# UC_Interface.net
KiCad netlist of a schematic drawn in Altium Designer
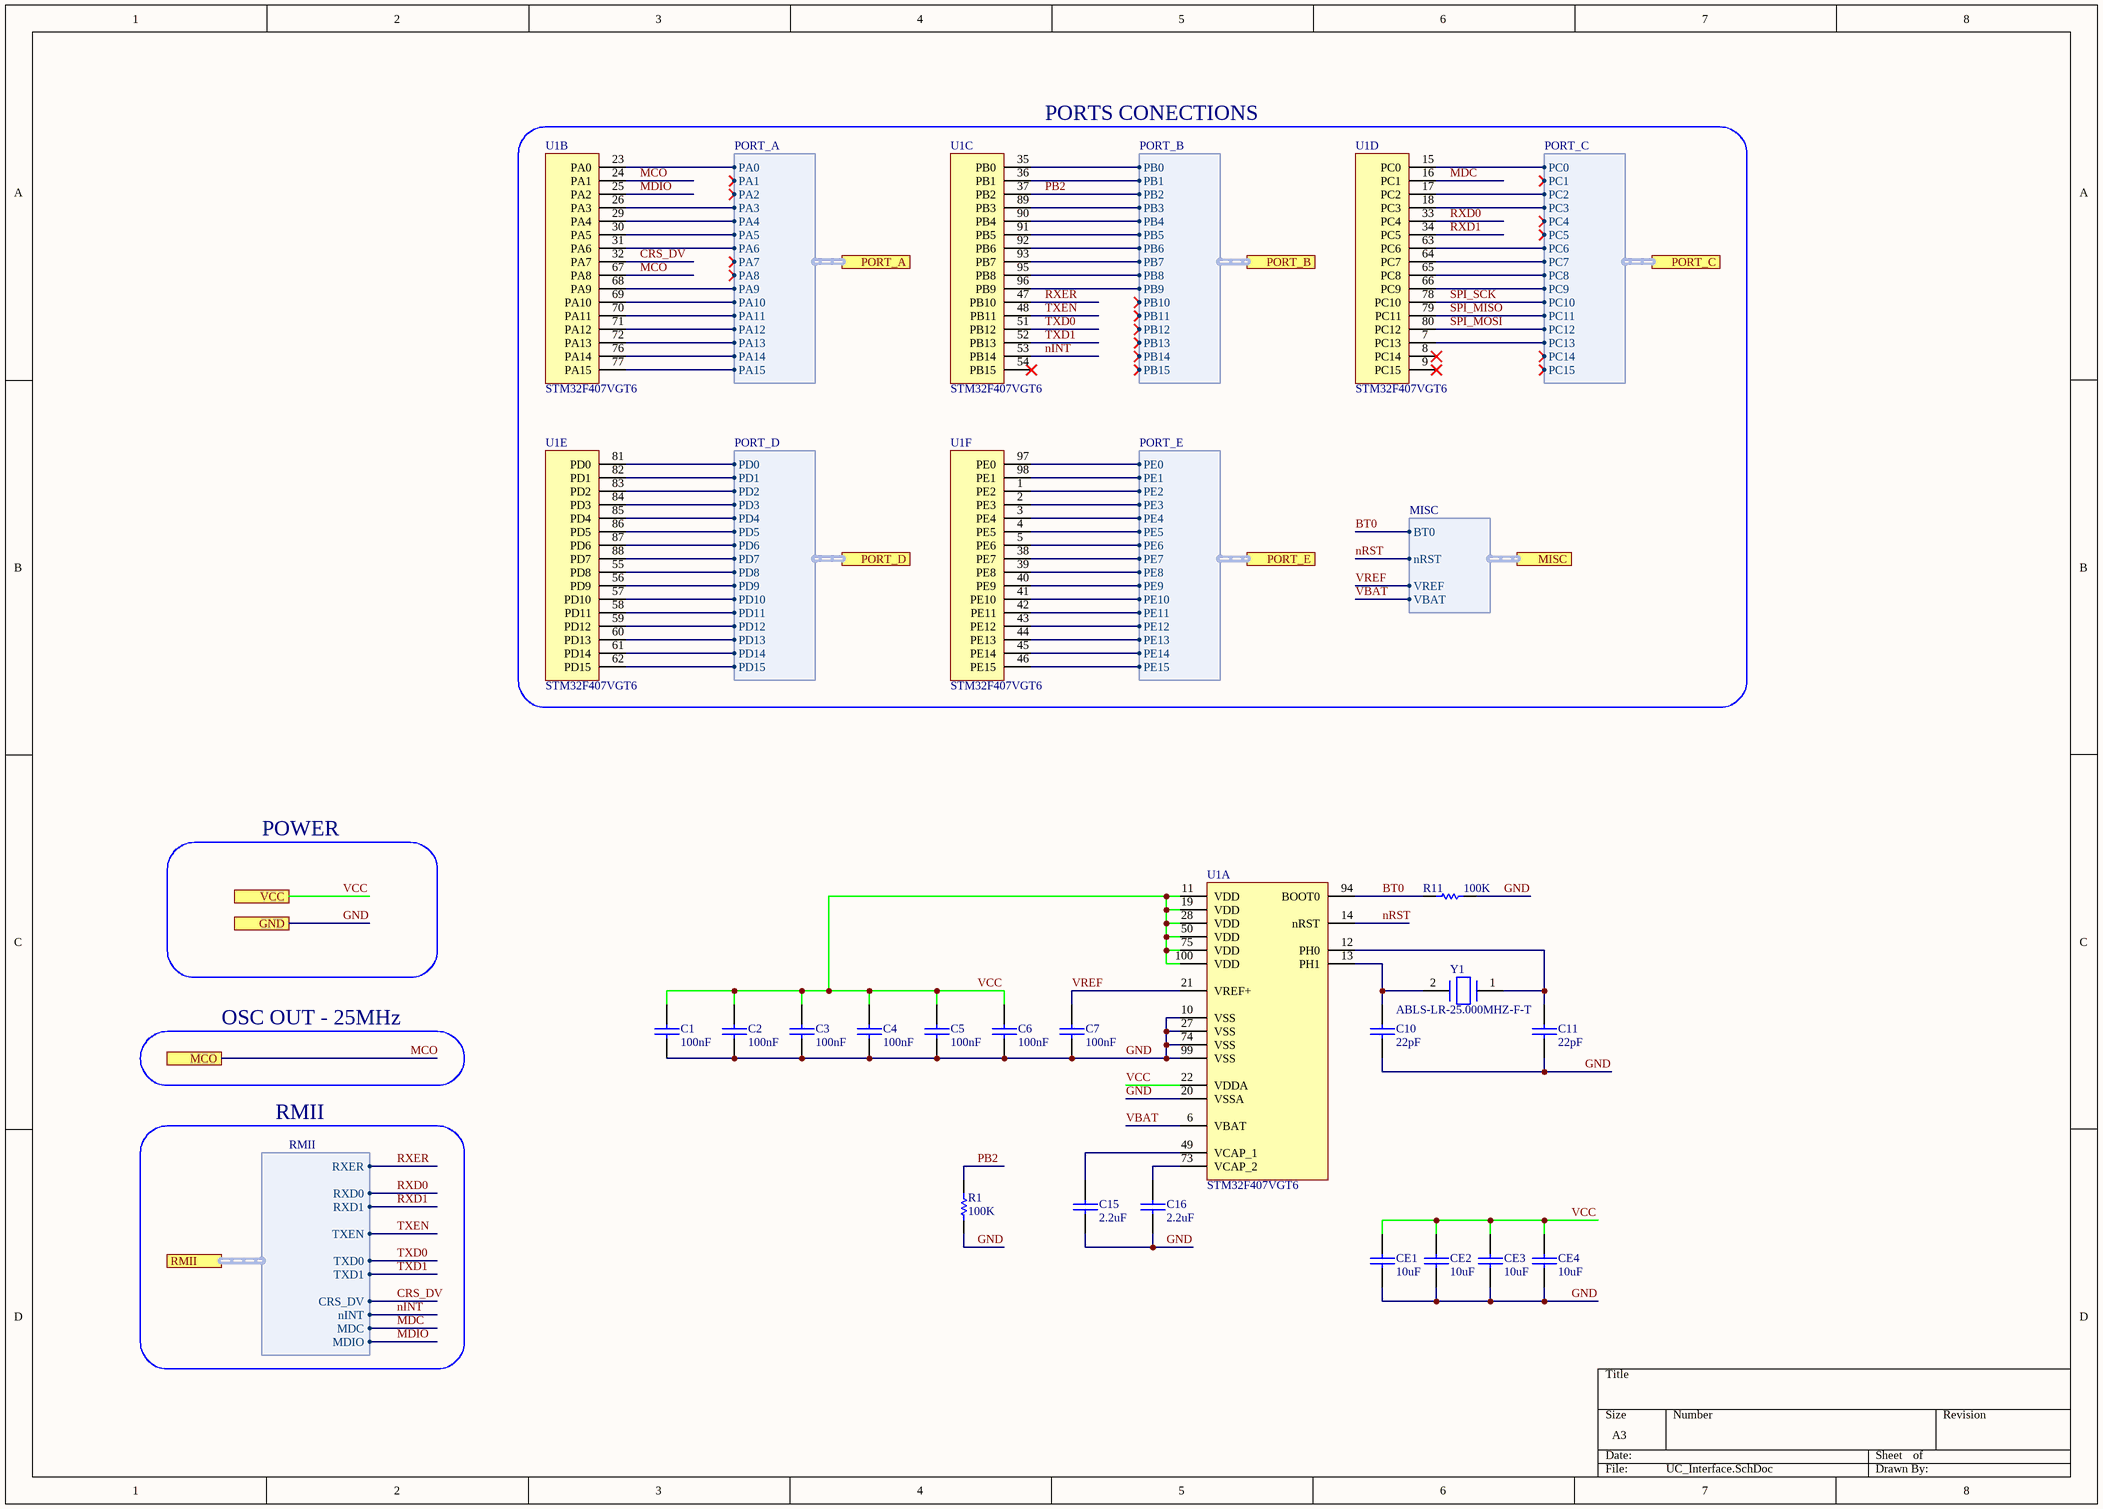
[diagram p0: UC_Interface.SchDoc]

(export (version "E")
  (design (tool "Eeschema 10.0.6"))
  (components
    (comp (ref "C1")
      (value "100nF")
      (footprint "0402-CAP-TDK")
      (libsource (lib "LIB2022 - Passives") (part "CAP-SMD"))
    )
    (comp (ref "C2")
      (value "100nF")
      (footprint "0402-CAP-TDK")
      (libsource (lib "LIB2022 - Passives") (part "CAP-SMD"))
    )
    (comp (ref "C3")
      (value "100nF")
      (footprint "0402-CAP-TDK")
      (libsource (lib "LIB2022 - Passives") (part "CAP-SMD"))
    )
    (comp (ref "C4")
      (value "100nF")
      (footprint "0402-CAP-TDK")
      (libsource (lib "LIB2022 - Passives") (part "CAP-SMD"))
    )
    (comp (ref "C5")
      (value "100nF")
      (footprint "0402-CAP-TDK")
      (libsource (lib "LIB2022 - Passives") (part "CAP-SMD"))
    )
    (comp (ref "C6")
      (value "100nF")
      (footprint "0402-CAP-TDK")
      (libsource (lib "LIB2022 - Passives") (part "CAP-SMD"))
    )
    (comp (ref "C7")
      (value "100nF")
      (footprint "0402-CAP-TDK")
      (libsource (lib "LIB2022 - Passives") (part "CAP-SMD"))
    )
    (comp (ref "C10")
      (value "22pF")
      (footprint "0603-CAP-TDK")
      (libsource (lib "LIB2022 - Passives") (part "CAP-SMD"))
    )
    (comp (ref "C11")
      (value "22pF")
      (footprint "0603-CAP-TDK")
      (libsource (lib "LIB2022 - Passives") (part "CAP-SMD"))
    )
    (comp (ref "C15")
      (value "2.2uF")
      (footprint "0603-CAP-TDK")
      (libsource (lib "LIB2022 - Passives") (part "CAP-SMD"))
    )
    (comp (ref "C16")
      (value "2.2uF")
      (footprint "0603-CAP-TDK")
      (libsource (lib "LIB2022 - Passives") (part "CAP-SMD"))
    )
    (comp (ref "CE1")
      (value "10uF")
      (footprint "0805-CAP-TDK")
      (libsource (lib "LIB2022 - Passives") (part "CAP-SMD"))
    )
    (comp (ref "CE2")
      (value "10uF")
      (footprint "0805-CAP-TDK")
      (libsource (lib "LIB2022 - Passives") (part "CAP-SMD"))
    )
    (comp (ref "CE3")
      (value "10uF")
      (footprint "0805-CAP-TDK")
      (libsource (lib "LIB2022 - Passives") (part "CAP-SMD"))
    )
    (comp (ref "CE4")
      (value "10uF")
      (footprint "0805-CAP-TDK")
      (libsource (lib "LIB2022 - Passives") (part "CAP-SMD"))
    )
    (comp (ref "R1")
      (value "100K")
      (footprint "0402-RES-PANASONIC")
      (libsource (lib "LIB2022 - Passives") (part "RES-SMD"))
    )
    (comp (ref "R11")
      (value "100K")
      (footprint "0402-RES-PANASONIC")
      (libsource (lib "LIB2022 - Passives") (part "RES-SMD"))
    )
    (comp (ref "U1")
      (value "STM32F407VGT6")
      (footprint "LQFP-100")
      (libsource (lib "LIB2022 - ICs") (part "STM32F407VGT6"))
    )
    (comp (ref "Y1")
      (value "ABLS-LR-25.000MHZ-F-T")
      (footprint "HC49S")
      (libsource (lib "LIB2022 - Crystals") (part "25.000MHz Crystal"))
    )
  )
  (nets
    (net (code "8") (name "/BT0") (class "Default")
      (node (ref "R11") (pin "1") (pinfunction "1_1") (pintype "passive"))
      (node (ref "U1") (pin "94") (pinfunction "BOOT0_94") (pintype "passive"))
    )
    (net (code "9") (name "/CRS_DV") (class "Default")
      (node (ref "U1") (pin "32") (pinfunction "PA7_32") (pintype "passive"))
    )
    (net (code "10") (name "/GND") (class "Default")
      (node (ref "C1") (pin "1") (pinfunction "1_1") (pintype "passive"))
      (node (ref "C10") (pin "1") (pinfunction "1_1") (pintype "passive"))
      (node (ref "C11") (pin "1") (pinfunction "1_1") (pintype "passive"))
      (node (ref "C15") (pin "1") (pinfunction "1_1") (pintype "passive"))
      (node (ref "C16") (pin "1") (pinfunction "1_1") (pintype "passive"))
      (node (ref "C2") (pin "1") (pinfunction "1_1") (pintype "passive"))
      (node (ref "C3") (pin "1") (pinfunction "1_1") (pintype "passive"))
      (node (ref "C4") (pin "1") (pinfunction "1_1") (pintype "passive"))
      (node (ref "C5") (pin "1") (pinfunction "1_1") (pintype "passive"))
      (node (ref "C6") (pin "1") (pinfunction "1_1") (pintype "passive"))
      (node (ref "C7") (pin "2") (pinfunction "2_2") (pintype "passive"))
      (node (ref "CE1") (pin "1") (pinfunction "1_1") (pintype "passive"))
      (node (ref "CE2") (pin "1") (pinfunction "1_1") (pintype "passive"))
      (node (ref "CE3") (pin "1") (pinfunction "1_1") (pintype "passive"))
      (node (ref "CE4") (pin "1") (pinfunction "1_1") (pintype "passive"))
      (node (ref "R1") (pin "1") (pinfunction "1_1") (pintype "passive"))
      (node (ref "R11") (pin "2") (pinfunction "2_2") (pintype "passive"))
      (node (ref "U1") (pin "10") (pinfunction "VSS_10") (pintype "passive"))
      (node (ref "U1") (pin "20") (pinfunction "VSSA_20") (pintype "passive"))
      (node (ref "U1") (pin "27") (pinfunction "VSS_27") (pintype "passive"))
      (node (ref "U1") (pin "74") (pinfunction "VSS_74") (pintype "passive"))
      (node (ref "U1") (pin "99") (pinfunction "VSS_99") (pintype "passive"))
    )
    (net (code "11") (name "/MCO") (class "Default")
      (node (ref "U1") (pin "24") (pinfunction "PA1_24") (pintype "passive"))
      (node (ref "U1") (pin "67") (pinfunction "PA8_67") (pintype "passive"))
    )
    (net (code "12") (name "/MDC") (class "Default")
      (node (ref "U1") (pin "16") (pinfunction "PC1_16") (pintype "passive"))
    )
    (net (code "13") (name "/MDIO") (class "Default")
      (node (ref "U1") (pin "25") (pinfunction "PA2_25") (pintype "passive"))
    )
    (net (code "14") (name "/PA0") (class "Default")
      (node (ref "U1") (pin "23") (pinfunction "PA0_23") (pintype "passive"))
    )
    (net (code "15") (name "/PA3") (class "Default")
      (node (ref "U1") (pin "26") (pinfunction "PA3_26") (pintype "passive"))
    )
    (net (code "16") (name "/PA4") (class "Default")
      (node (ref "U1") (pin "29") (pinfunction "PA4_29") (pintype "passive"))
    )
    (net (code "17") (name "/PA5") (class "Default")
      (node (ref "U1") (pin "30") (pinfunction "PA5_30") (pintype "passive"))
    )
    (net (code "18") (name "/PA6") (class "Default")
      (node (ref "U1") (pin "31") (pinfunction "PA6_31") (pintype "passive"))
    )
    (net (code "19") (name "/PA9") (class "Default")
      (node (ref "U1") (pin "68") (pinfunction "PA9_68") (pintype "passive"))
    )
    (net (code "20") (name "/PA10") (class "Default")
      (node (ref "U1") (pin "69") (pinfunction "PA10_69") (pintype "passive"))
    )
    (net (code "21") (name "/PA11") (class "Default")
      (node (ref "U1") (pin "70") (pinfunction "PA11_70") (pintype "passive"))
    )
    (net (code "22") (name "/PA12") (class "Default")
      (node (ref "U1") (pin "71") (pinfunction "PA12_71") (pintype "passive"))
    )
    (net (code "23") (name "/PA13") (class "Default")
      (node (ref "U1") (pin "72") (pinfunction "PA13_72") (pintype "passive"))
    )
    (net (code "24") (name "/PA14") (class "Default")
      (node (ref "U1") (pin "76") (pinfunction "PA14_76") (pintype "passive"))
    )
    (net (code "25") (name "/PA15") (class "Default")
      (node (ref "U1") (pin "77") (pinfunction "PA15_77") (pintype "passive"))
    )
    (net (code "26") (name "/PB0") (class "Default")
      (node (ref "U1") (pin "35") (pinfunction "PB0_35") (pintype "passive"))
    )
    (net (code "27") (name "/PB1") (class "Default")
      (node (ref "U1") (pin "36") (pinfunction "PB1_36") (pintype "passive"))
    )
    (net (code "28") (name "/PB2") (class "Default")
      (node (ref "R1") (pin "2") (pinfunction "2_2") (pintype "passive"))
      (node (ref "U1") (pin "37") (pinfunction "PB2_37") (pintype "passive"))
    )
    (net (code "29") (name "/PB3") (class "Default")
      (node (ref "U1") (pin "89") (pinfunction "PB3_89") (pintype "passive"))
    )
    (net (code "30") (name "/PB4") (class "Default")
      (node (ref "U1") (pin "90") (pinfunction "PB4_90") (pintype "passive"))
    )
    (net (code "31") (name "/PB5") (class "Default")
      (node (ref "U1") (pin "91") (pinfunction "PB5_91") (pintype "passive"))
    )
    (net (code "32") (name "/PB6") (class "Default")
      (node (ref "U1") (pin "92") (pinfunction "PB6_92") (pintype "passive"))
    )
    (net (code "33") (name "/PB7") (class "Default")
      (node (ref "U1") (pin "93") (pinfunction "PB7_93") (pintype "passive"))
    )
    (net (code "34") (name "/PB8") (class "Default")
      (node (ref "U1") (pin "95") (pinfunction "PB8_95") (pintype "passive"))
    )
    (net (code "35") (name "/PB9") (class "Default")
      (node (ref "U1") (pin "96") (pinfunction "PB9_96") (pintype "passive"))
    )
    (net (code "36") (name "/PC0") (class "Default")
      (node (ref "U1") (pin "15") (pinfunction "PC0_15") (pintype "passive"))
    )
    (net (code "37") (name "/PC2") (class "Default")
      (node (ref "U1") (pin "17") (pinfunction "PC2_17") (pintype "passive"))
    )
    (net (code "38") (name "/PC3") (class "Default")
      (node (ref "U1") (pin "18") (pinfunction "PC3_18") (pintype "passive"))
    )
    (net (code "39") (name "/PC6") (class "Default")
      (node (ref "U1") (pin "63") (pinfunction "PC6_63") (pintype "passive"))
    )
    (net (code "40") (name "/PC7") (class "Default")
      (node (ref "U1") (pin "64") (pinfunction "PC7_64") (pintype "passive"))
    )
    (net (code "41") (name "/PC8") (class "Default")
      (node (ref "U1") (pin "65") (pinfunction "PC8_65") (pintype "passive"))
    )
    (net (code "42") (name "/PC9") (class "Default")
      (node (ref "U1") (pin "66") (pinfunction "PC9_66") (pintype "passive"))
    )
    (net (code "43") (name "/PC13") (class "Default")
      (node (ref "U1") (pin "7") (pinfunction "PC13_7") (pintype "passive"))
    )
    (net (code "44") (name "/PD0") (class "Default")
      (node (ref "U1") (pin "81") (pinfunction "PD0_81") (pintype "passive"))
    )
    (net (code "45") (name "/PD1") (class "Default")
      (node (ref "U1") (pin "82") (pinfunction "PD1_82") (pintype "passive"))
    )
    (net (code "46") (name "/PD2") (class "Default")
      (node (ref "U1") (pin "83") (pinfunction "PD2_83") (pintype "passive"))
    )
    (net (code "47") (name "/PD3") (class "Default")
      (node (ref "U1") (pin "84") (pinfunction "PD3_84") (pintype "passive"))
    )
    (net (code "48") (name "/PD4") (class "Default")
      (node (ref "U1") (pin "85") (pinfunction "PD4_85") (pintype "passive"))
    )
    (net (code "49") (name "/PD5") (class "Default")
      (node (ref "U1") (pin "86") (pinfunction "PD5_86") (pintype "passive"))
    )
    (net (code "50") (name "/PD6") (class "Default")
      (node (ref "U1") (pin "87") (pinfunction "PD6_87") (pintype "passive"))
    )
    (net (code "51") (name "/PD7") (class "Default")
      (node (ref "U1") (pin "88") (pinfunction "PD7_88") (pintype "passive"))
    )
    (net (code "52") (name "/PD8") (class "Default")
      (node (ref "U1") (pin "55") (pinfunction "PD8_55") (pintype "passive"))
    )
    (net (code "53") (name "/PD9") (class "Default")
      (node (ref "U1") (pin "56") (pinfunction "PD9_56") (pintype "passive"))
    )
    (net (code "54") (name "/PD10") (class "Default")
      (node (ref "U1") (pin "57") (pinfunction "PD10_57") (pintype "passive"))
    )
    (net (code "55") (name "/PD11") (class "Default")
      (node (ref "U1") (pin "58") (pinfunction "PD11_58") (pintype "passive"))
    )
    (net (code "56") (name "/PD12") (class "Default")
      (node (ref "U1") (pin "59") (pinfunction "PD12_59") (pintype "passive"))
    )
    (net (code "57") (name "/PD13") (class "Default")
      (node (ref "U1") (pin "60") (pinfunction "PD13_60") (pintype "passive"))
    )
    (net (code "58") (name "/PD14") (class "Default")
      (node (ref "U1") (pin "61") (pinfunction "PD14_61") (pintype "passive"))
    )
    (net (code "59") (name "/PD15") (class "Default")
      (node (ref "U1") (pin "62") (pinfunction "PD15_62") (pintype "passive"))
    )
    (net (code "60") (name "/PE0") (class "Default")
      (node (ref "U1") (pin "97") (pinfunction "PE0_97") (pintype "passive"))
    )
    (net (code "61") (name "/PE1") (class "Default")
      (node (ref "U1") (pin "98") (pinfunction "PE1_98") (pintype "passive"))
    )
    (net (code "62") (name "/PE2") (class "Default")
      (node (ref "U1") (pin "1") (pinfunction "PE2_1") (pintype "passive"))
    )
    (net (code "63") (name "/PE3") (class "Default")
      (node (ref "U1") (pin "2") (pinfunction "PE3_2") (pintype "passive"))
    )
    (net (code "64") (name "/PE4") (class "Default")
      (node (ref "U1") (pin "3") (pinfunction "PE4_3") (pintype "passive"))
    )
    (net (code "65") (name "/PE5") (class "Default")
      (node (ref "U1") (pin "4") (pinfunction "PE5_4") (pintype "passive"))
    )
    (net (code "66") (name "/PE6") (class "Default")
      (node (ref "U1") (pin "5") (pinfunction "PE6_5") (pintype "passive"))
    )
    (net (code "67") (name "/PE7") (class "Default")
      (node (ref "U1") (pin "38") (pinfunction "PE7_38") (pintype "passive"))
    )
    (net (code "68") (name "/PE8") (class "Default")
      (node (ref "U1") (pin "39") (pinfunction "PE8_39") (pintype "passive"))
    )
    (net (code "69") (name "/PE9") (class "Default")
      (node (ref "U1") (pin "40") (pinfunction "PE9_40") (pintype "passive"))
    )
    (net (code "70") (name "/PE10") (class "Default")
      (node (ref "U1") (pin "41") (pinfunction "PE10_41") (pintype "passive"))
    )
    (net (code "71") (name "/PE11") (class "Default")
      (node (ref "U1") (pin "42") (pinfunction "PE11_42") (pintype "passive"))
    )
    (net (code "72") (name "/PE12") (class "Default")
      (node (ref "U1") (pin "43") (pinfunction "PE12_43") (pintype "passive"))
    )
    (net (code "73") (name "/PE13") (class "Default")
      (node (ref "U1") (pin "44") (pinfunction "PE13_44") (pintype "passive"))
    )
    (net (code "74") (name "/PE14") (class "Default")
      (node (ref "U1") (pin "45") (pinfunction "PE14_45") (pintype "passive"))
    )
    (net (code "75") (name "/PE15") (class "Default")
      (node (ref "U1") (pin "46") (pinfunction "PE15_46") (pintype "passive"))
    )
    (net (code "76") (name "/RXD0") (class "Default")
      (node (ref "U1") (pin "33") (pinfunction "PC4_33") (pintype "passive"))
    )
    (net (code "77") (name "/RXD1") (class "Default")
      (node (ref "U1") (pin "34") (pinfunction "PC5_34") (pintype "passive"))
    )
    (net (code "78") (name "/RXER") (class "Default")
      (node (ref "U1") (pin "47") (pinfunction "PB10_47") (pintype "passive"))
    )
    (net (code "79") (name "/SPI_MISO") (class "Default")
      (node (ref "U1") (pin "79") (pinfunction "PC11_79") (pintype "passive"))
    )
    (net (code "80") (name "/SPI_MOSI") (class "Default")
      (node (ref "U1") (pin "80") (pinfunction "PC12_80") (pintype "passive"))
    )
    (net (code "81") (name "/SPI_SCK") (class "Default")
      (node (ref "U1") (pin "78") (pinfunction "PC10_78") (pintype "passive"))
    )
    (net (code "82") (name "/TXD0") (class "Default")
      (node (ref "U1") (pin "51") (pinfunction "PB12_51") (pintype "passive"))
    )
    (net (code "83") (name "/TXD1") (class "Default")
      (node (ref "U1") (pin "52") (pinfunction "PB13_52") (pintype "passive"))
    )
    (net (code "84") (name "/TXEN") (class "Default")
      (node (ref "U1") (pin "48") (pinfunction "PB11_48") (pintype "passive"))
    )
    (net (code "85") (name "/VBAT") (class "Default")
      (node (ref "U1") (pin "6") (pinfunction "VBAT_6") (pintype "passive"))
    )
    (net (code "86") (name "/VCC") (class "Default")
      (node (ref "C1") (pin "2") (pinfunction "2_2") (pintype "passive"))
      (node (ref "C2") (pin "2") (pinfunction "2_2") (pintype "passive"))
      (node (ref "C3") (pin "2") (pinfunction "2_2") (pintype "passive"))
      (node (ref "C4") (pin "2") (pinfunction "2_2") (pintype "passive"))
      (node (ref "C5") (pin "2") (pinfunction "2_2") (pintype "passive"))
      (node (ref "C6") (pin "2") (pinfunction "2_2") (pintype "passive"))
      (node (ref "CE1") (pin "2") (pinfunction "2_2") (pintype "passive"))
      (node (ref "CE2") (pin "2") (pinfunction "2_2") (pintype "passive"))
      (node (ref "CE3") (pin "2") (pinfunction "2_2") (pintype "passive"))
      (node (ref "CE4") (pin "2") (pinfunction "2_2") (pintype "passive"))
      (node (ref "U1") (pin "100") (pinfunction "VDD_100") (pintype "passive"))
      (node (ref "U1") (pin "11") (pinfunction "VDD_11") (pintype "passive"))
      (node (ref "U1") (pin "19") (pinfunction "VDD_19") (pintype "passive"))
      (node (ref "U1") (pin "22") (pinfunction "VDDA_22") (pintype "passive"))
      (node (ref "U1") (pin "28") (pinfunction "VDD_28") (pintype "passive"))
      (node (ref "U1") (pin "50") (pinfunction "VDD_50") (pintype "passive"))
      (node (ref "U1") (pin "75") (pinfunction "VDD_75") (pintype "passive"))
    )
    (net (code "87") (name "/VREF") (class "Default")
      (node (ref "C7") (pin "1") (pinfunction "1_1") (pintype "passive"))
      (node (ref "U1") (pin "21") (pinfunction "VREF+_21") (pintype "passive"))
    )
    (net (code "88") (name "/nINT") (class "Default")
      (node (ref "U1") (pin "53") (pinfunction "PB14_53") (pintype "passive"))
    )
    (net (code "89") (name "/nRST") (class "Default")
      (node (ref "U1") (pin "14") (pinfunction "nRST_14") (pintype "passive"))
    )
    (net (code "97") (name "Net-(U1A-PH0)") (class "Default")
      (node (ref "C11") (pin "2") (pinfunction "2_2") (pintype "passive"))
      (node (ref "U1") (pin "12") (pinfunction "PH0_12") (pintype "passive"))
      (node (ref "Y1") (pin "1") (pinfunction "1_1") (pintype "passive"))
    )
    (net (code "98") (name "Net-(U1A-PH1)") (class "Default")
      (node (ref "C10") (pin "2") (pinfunction "2_2") (pintype "passive"))
      (node (ref "U1") (pin "13") (pinfunction "PH1_13") (pintype "passive"))
      (node (ref "Y1") (pin "2") (pinfunction "2_2") (pintype "passive"))
    )
    (net (code "99") (name "Net-(U1A-VCAP_1)") (class "Default")
      (node (ref "C15") (pin "2") (pinfunction "2_2") (pintype "passive"))
      (node (ref "U1") (pin "49") (pinfunction "VCAP_1_49") (pintype "passive"))
    )
    (net (code "100") (name "Net-(U1A-VCAP_2)") (class "Default")
      (node (ref "C16") (pin "2") (pinfunction "2_2") (pintype "passive"))
      (node (ref "U1") (pin "73") (pinfunction "VCAP_2_73") (pintype "passive"))
    )
    (net (code "101") (name "unconnected-(U1C-PB15-Pad54)") (class "Default")
      (node (ref "U1") (pin "54") (pinfunction "PB15_54") (pintype "passive+no_connect"))
    )
    (net (code "102") (name "unconnected-(U1D-PC14-Pad8)") (class "Default")
      (node (ref "U1") (pin "8") (pinfunction "PC14_8") (pintype "passive+no_connect"))
    )
    (net (code "103") (name "unconnected-(U1D-PC15-Pad9)") (class "Default")
      (node (ref "U1") (pin "9") (pinfunction "PC15_9") (pintype "passive+no_connect"))
    )
  )
)
